# CC3000_WiFi_Breakout.net
KiCad netlist of a schematic drawn in EAGLE
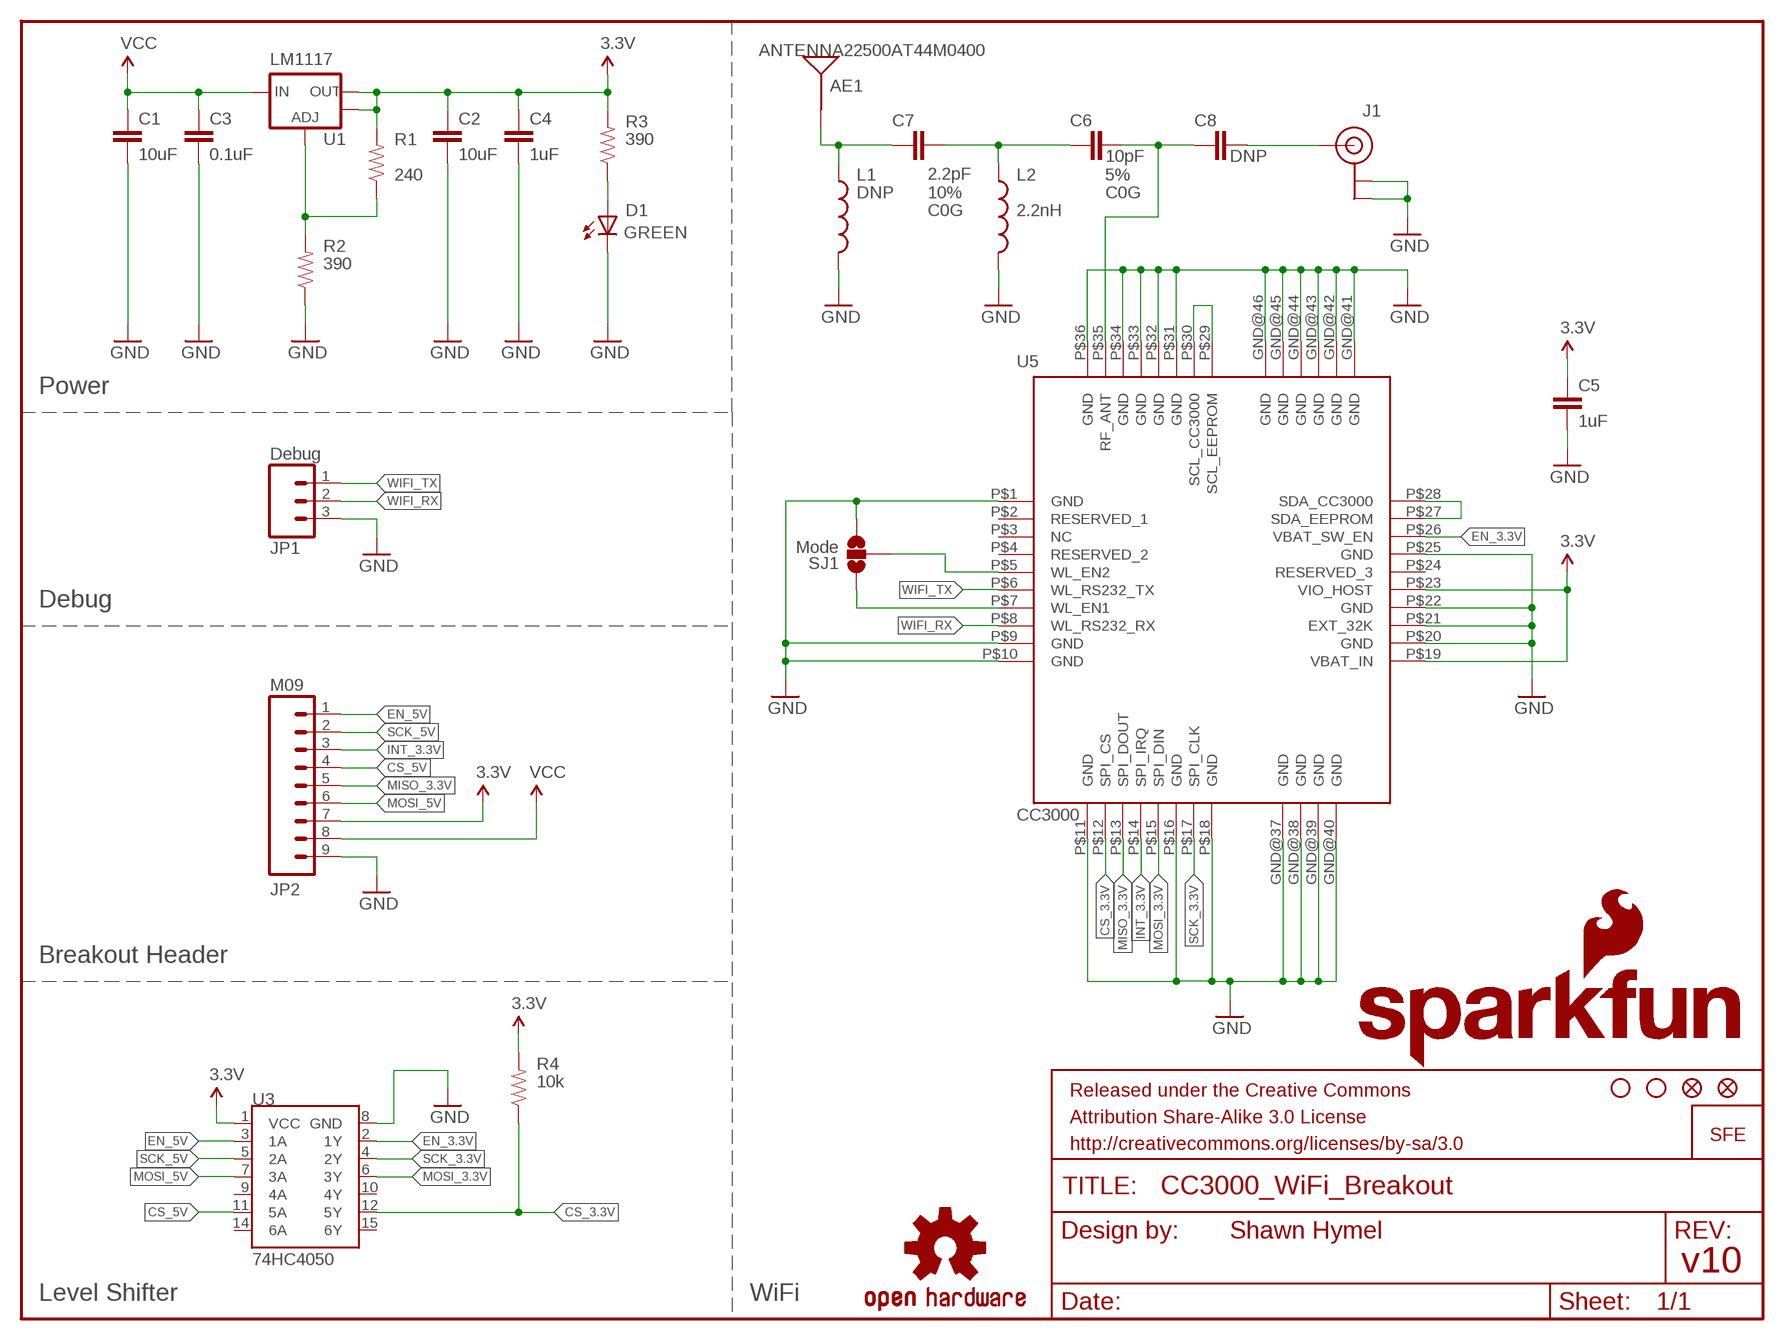
[diagram p0: schematic, sheet 1]

(export (version "E")
  (design (tool "Eeschema 10.0.6"))
  (components
    (comp (ref "AE1")
      (value "ANTENNA22500AT44M0400")
      (footprint "eagle-import:ANTENNA-CHIP_2500AT44M0400")
      (libsource (lib "eagle-import") (part "ANTENNA22500AT44M0400"))
    )
    (comp (ref "C1")
      (value "10uF")
      (footprint "eagle-import:0805")
      (libsource (lib "eagle-import") (part "CAP0805"))
    )
    (comp (ref "C2")
      (value "10uF")
      (footprint "eagle-import:0805")
      (libsource (lib "eagle-import") (part "CAP0805"))
    )
    (comp (ref "C3")
      (value "0.1uF")
      (footprint "eagle-import:0603-CAP")
      (libsource (lib "eagle-import") (part "CAP0603-CAP"))
    )
    (comp (ref "C4")
      (value "1uF")
      (footprint "eagle-import:0805")
      (libsource (lib "eagle-import") (part "CAP0805"))
    )
    (comp (ref "C5")
      (value "1uF")
      (footprint "eagle-import:0805")
      (libsource (lib "eagle-import") (part "CAP0805"))
    )
    (comp (ref "C6")
      (value "10pF")
      (footprint "eagle-import:0603-CAP")
      (fields (field (name "COEFF") "C0G") (field (name "TOL") "5%"))
      (libsource (lib "eagle-import") (part "CAP0603-CAP"))
    )
    (comp (ref "C7")
      (value "2.2pF")
      (footprint "eagle-import:0603-CAP")
      (fields (field (name "COEFF") "C0G") (field (name "TOL") "10%"))
      (libsource (lib "eagle-import") (part "CAP0603-CAP"))
    )
    (comp (ref "C8")
      (value "DNP")
      (footprint "eagle-import:0603-CAP")
      (libsource (lib "eagle-import") (part "CAP0603-CAP"))
    )
    (comp (ref "D1")
      (value "GREEN")
      (footprint "eagle-import:LED-0603")
      (libsource (lib "eagle-import") (part "LED-GREEN0603"))
    )
    (comp (ref "FID1")
      (value "FIDUCIAL1X2")
      (footprint "eagle-import:FIDUCIAL-1X2")
      (libsource (lib "eagle-import") (part "FIDUCIAL1X2"))
    )
    (comp (ref "FID2")
      (value "FIDUCIAL1X2")
      (footprint "eagle-import:FIDUCIAL-1X2")
      (libsource (lib "eagle-import") (part "FIDUCIAL1X2"))
    )
    (comp (ref "FRAME1")
      (value "FRAME-LETTER")
      (footprint "eagle-import:CREATIVE_COMMONS")
      (libsource (lib "eagle-import") (part "FRAME-LETTER"))
    )
    (comp (ref "J1")
      (value "U.FL")
      (footprint "eagle-import:U.FL")
      (libsource (lib "eagle-import") (part "U.FL"))
    )
    (comp (ref "JP1")
      (value "Debug")
      (footprint "eagle-import:1X03")
      (libsource (lib "eagle-import") (part "M03PTH"))
    )
    (comp (ref "JP2")
      (value "M09")
      (footprint "eagle-import:1X09")
      (libsource (lib "eagle-import") (part "M09"))
    )
    (comp (ref "L1")
      (value "DNP")
      (footprint "eagle-import:0603")
      (libsource (lib "eagle-import") (part "INDUCTOR0603"))
    )
    (comp (ref "L2")
      (value "2.2nH")
      (footprint "eagle-import:0603")
      (libsource (lib "eagle-import") (part "INDUCTOR0603"))
    )
    (comp (ref "LOGO1")
      (value "OSHW-LOGOS")
      (footprint "eagle-import:OSHW-LOGO-S")
      (libsource (lib "eagle-import") (part "OSHW-LOGOS"))
    )
    (comp (ref "LOGO3")
      (value "LOGO-SFESK")
      (footprint "eagle-import:SFE-LOGO-FLAME")
      (libsource (lib "eagle-import") (part "LOGO-SFESK"))
    )
    (comp (ref "LOGO4")
      (value "SFE_LOGO_NAME_FLAME.1_INCH")
      (footprint "eagle-import:SFE_LOGO_NAME_FLAME_.1")
      (libsource (lib "eagle-import") (part "SFE_LOGO_NAME_FLAME.1_INCH"))
    )
    (comp (ref "R1")
      (value "240")
      (footprint "eagle-import:0603-RES")
      (libsource (lib "eagle-import") (part "RESISTOR0603"))
    )
    (comp (ref "R2")
      (value "390")
      (footprint "eagle-import:0603-RES")
      (libsource (lib "eagle-import") (part "RESISTOR0603"))
    )
    (comp (ref "R3")
      (value "390")
      (footprint "eagle-import:0603-RES")
      (libsource (lib "eagle-import") (part "RESISTOR0603-RES"))
    )
    (comp (ref "R4")
      (value "10k")
      (footprint "eagle-import:0603-RES")
      (libsource (lib "eagle-import") (part "RESISTOR0603-RES"))
    )
    (comp (ref "SJ1")
      (value "Mode")
      (footprint "eagle-import:SJ_3_PASTE1&2")
      (libsource (lib "eagle-import") (part "SOLDERJUMPER_2WAYPASTE1&2"))
    )
    (comp (ref "STANDOFF1")
      (value "STAND-OFF")
      (footprint "eagle-import:STAND-OFF")
      (libsource (lib "eagle-import") (part "STAND-OFF"))
    )
    (comp (ref "STANDOFF2")
      (value "STAND-OFF")
      (footprint "eagle-import:STAND-OFF")
      (libsource (lib "eagle-import") (part "STAND-OFF"))
    )
    (comp (ref "U1")
      (value "LM1117")
      (footprint "eagle-import:SOT223")
      (libsource (lib "eagle-import") (part "V_REG_LM1117SOT223"))
    )
    (comp (ref "U3")
      (value "74HC4050")
      (footprint "eagle-import:SO016")
      (libsource (lib "eagle-import") (part "HEX_CONVERTER"))
    )
    (comp (ref "U5")
      (value "CC3000")
      (footprint "eagle-import:QFN-46_CC3000")
      (libsource (lib "eagle-import") (part "CC3000"))
    )
  )
  (nets
    (net (code "1") (name "3.3V") (class "Default")
      (node (ref "C2") (pin "1") (pinfunction "1_1") (pintype "passive"))
      (node (ref "C4") (pin "1") (pinfunction "1_1") (pintype "passive"))
      (node (ref "C5") (pin "1") (pinfunction "1_1") (pintype "passive"))
      (node (ref "JP2") (pin "7") (pinfunction "7_7") (pintype "passive"))
      (node (ref "R1") (pin "2") (pinfunction "2_2") (pintype "passive"))
      (node (ref "R3") (pin "2") (pinfunction "2_2") (pintype "passive"))
      (node (ref "R4") (pin "2") (pinfunction "2_2") (pintype "passive"))
      (node (ref "U1") (pin "2") (pinfunction "OUT_2") (pintype "output"))
      (node (ref "U1") (pin "4") (pinfunction "OUT_4") (pintype "output"))
      (node (ref "U3") (pin "1") (pinfunction "VCC_1") (pintype "bidirectional"))
      (node (ref "U5") (pin "P$19") (pinfunction "VBAT_IN_P$19") (pintype "bidirectional"))
      (node (ref "U5") (pin "P$23") (pinfunction "VIO_HOST_P$23") (pintype "bidirectional"))
    )
    (net (code "2") (name "CS_3.3V") (class "Default")
      (node (ref "R4") (pin "1") (pinfunction "1_1") (pintype "passive"))
      (node (ref "U3") (pin "12") (pinfunction "5Y_12") (pintype "bidirectional"))
      (node (ref "U5") (pin "P$12") (pinfunction "SPI_CS_P$12") (pintype "bidirectional"))
    )
    (net (code "3") (name "CS_5V") (class "Default")
      (node (ref "JP2") (pin "4") (pinfunction "4_4") (pintype "passive"))
      (node (ref "U3") (pin "11") (pinfunction "5A_11") (pintype "bidirectional"))
    )
    (net (code "4") (name "EN_3.3V") (class "Default")
      (node (ref "U3") (pin "2") (pinfunction "1Y_2") (pintype "bidirectional"))
      (node (ref "U5") (pin "P$26") (pinfunction "VBAT_SW_EN_P$26") (pintype "bidirectional"))
    )
    (net (code "5") (name "EN_5V") (class "Default")
      (node (ref "JP2") (pin "1") (pinfunction "1_1") (pintype "passive"))
      (node (ref "U3") (pin "3") (pinfunction "1A_3") (pintype "bidirectional"))
    )
    (net (code "6") (name "GND") (class "Default")
      (node (ref "C1") (pin "2") (pinfunction "2_2") (pintype "passive"))
      (node (ref "C2") (pin "2") (pinfunction "2_2") (pintype "passive"))
      (node (ref "C3") (pin "2") (pinfunction "2_2") (pintype "passive"))
      (node (ref "C4") (pin "2") (pinfunction "2_2") (pintype "passive"))
      (node (ref "C5") (pin "2") (pinfunction "2_2") (pintype "passive"))
      (node (ref "D1") (pin "C") (pinfunction "C_C") (pintype "passive"))
      (node (ref "J1") (pin "P$1") (pinfunction "GND_P$1") (pintype "bidirectional"))
      (node (ref "J1") (pin "P$2") (pinfunction "GND_P$2") (pintype "bidirectional"))
      (node (ref "JP1") (pin "3") (pinfunction "3_3") (pintype "passive"))
      (node (ref "JP2") (pin "9") (pinfunction "9_9") (pintype "passive"))
      (node (ref "L1") (pin "2") (pinfunction "2_2") (pintype "passive"))
      (node (ref "L2") (pin "2") (pinfunction "2_2") (pintype "passive"))
      (node (ref "R2") (pin "1") (pinfunction "1_1") (pintype "passive"))
      (node (ref "SJ1") (pin "3") (pinfunction "3_3") (pintype "passive"))
      (node (ref "U3") (pin "8") (pinfunction "GND_8") (pintype "bidirectional"))
      (node (ref "U5") (pin "GND@37") (pinfunction "GND_GND@37") (pintype "bidirectional"))
      (node (ref "U5") (pin "GND@38") (pinfunction "GND_GND@38") (pintype "bidirectional"))
      (node (ref "U5") (pin "GND@39") (pinfunction "GND_GND@39") (pintype "bidirectional"))
      (node (ref "U5") (pin "GND@40") (pinfunction "GND_GND@40") (pintype "bidirectional"))
      (node (ref "U5") (pin "GND@41") (pinfunction "GND_GND@41") (pintype "bidirectional"))
      (node (ref "U5") (pin "GND@42") (pinfunction "GND_GND@42") (pintype "bidirectional"))
      (node (ref "U5") (pin "GND@43") (pinfunction "GND_GND@43") (pintype "bidirectional"))
      (node (ref "U5") (pin "GND@44") (pinfunction "GND_GND@44") (pintype "bidirectional"))
      (node (ref "U5") (pin "GND@45") (pinfunction "GND_GND@45") (pintype "bidirectional"))
      (node (ref "U5") (pin "GND@46") (pinfunction "GND_GND@46") (pintype "bidirectional"))
      (node (ref "U5") (pin "P$1") (pinfunction "GND_P$1") (pintype "bidirectional"))
      (node (ref "U5") (pin "P$10") (pinfunction "GND_P$10") (pintype "bidirectional"))
      (node (ref "U5") (pin "P$11") (pinfunction "GND_P$11") (pintype "bidirectional"))
      (node (ref "U5") (pin "P$16") (pinfunction "GND_P$16") (pintype "bidirectional"))
      (node (ref "U5") (pin "P$18") (pinfunction "GND_P$18") (pintype "bidirectional"))
      (node (ref "U5") (pin "P$20") (pinfunction "GND_P$20") (pintype "bidirectional"))
      (node (ref "U5") (pin "P$21") (pinfunction "EXT_32K_P$21") (pintype "bidirectional"))
      (node (ref "U5") (pin "P$22") (pinfunction "GND_P$22") (pintype "bidirectional"))
      (node (ref "U5") (pin "P$25") (pinfunction "GND_P$25") (pintype "bidirectional"))
      (node (ref "U5") (pin "P$31") (pinfunction "GND_P$31") (pintype "bidirectional"))
      (node (ref "U5") (pin "P$32") (pinfunction "GND_P$32") (pintype "bidirectional"))
      (node (ref "U5") (pin "P$33") (pinfunction "GND_P$33") (pintype "bidirectional"))
      (node (ref "U5") (pin "P$34") (pinfunction "GND_P$34") (pintype "bidirectional"))
      (node (ref "U5") (pin "P$36") (pinfunction "GND_P$36") (pintype "bidirectional"))
      (node (ref "U5") (pin "P$9") (pinfunction "GND_P$9") (pintype "bidirectional"))
    )
    (net (code "7") (name "INT_3.3V") (class "Default")
      (node (ref "JP2") (pin "3") (pinfunction "3_3") (pintype "passive"))
      (node (ref "U5") (pin "P$14") (pinfunction "SPI_IRQ_P$14") (pintype "bidirectional"))
    )
    (net (code "8") (name "MISO_3.3V") (class "Default")
      (node (ref "JP2") (pin "5") (pinfunction "5_5") (pintype "passive"))
      (node (ref "U5") (pin "P$13") (pinfunction "SPI_DOUT_P$13") (pintype "bidirectional"))
    )
    (net (code "9") (name "MOSI_3.3V") (class "Default")
      (node (ref "U3") (pin "6") (pinfunction "3Y_6") (pintype "bidirectional"))
      (node (ref "U5") (pin "P$15") (pinfunction "SPI_DIN_P$15") (pintype "bidirectional"))
    )
    (net (code "10") (name "MOSI_5V") (class "Default")
      (node (ref "JP2") (pin "6") (pinfunction "6_6") (pintype "passive"))
      (node (ref "U3") (pin "7") (pinfunction "3A_7") (pintype "bidirectional"))
    )
    (net (code "11") (name "Net-(AE1-SIGNAL)") (class "Default")
      (node (ref "AE1") (pin "FEED") (pinfunction "SIGNAL_FEED") (pintype "bidirectional"))
      (node (ref "C7") (pin "1") (pinfunction "1_1") (pintype "passive"))
      (node (ref "L1") (pin "1") (pinfunction "1_1") (pintype "passive"))
    )
    (net (code "12") (name "Net-(C6-Pad1)") (class "Default")
      (node (ref "C6") (pin "1") (pinfunction "1_1") (pintype "passive"))
      (node (ref "C7") (pin "2") (pinfunction "2_2") (pintype "passive"))
      (node (ref "L2") (pin "1") (pinfunction "1_1") (pintype "passive"))
    )
    (net (code "13") (name "Net-(D1-PadA)") (class "Default")
      (node (ref "D1") (pin "A") (pinfunction "A_A") (pintype "passive"))
      (node (ref "R3") (pin "1") (pinfunction "1_1") (pintype "passive"))
    )
    (net (code "14") (name "Net-(J1-SIGNAL)") (class "Default")
      (node (ref "C8") (pin "2") (pinfunction "2_2") (pintype "passive"))
      (node (ref "J1") (pin "P$3") (pinfunction "SIGNAL_P$3") (pintype "bidirectional"))
    )
    (net (code "15") (name "Net-(U1-ADJ)") (class "Default")
      (node (ref "R1") (pin "1") (pinfunction "1_1") (pintype "passive"))
      (node (ref "R2") (pin "2") (pinfunction "2_2") (pintype "passive"))
      (node (ref "U1") (pin "1") (pinfunction "ADJ_1") (pintype "input"))
    )
    (net (code "16") (name "Net-(U5-RF_ANT)") (class "Default")
      (node (ref "C6") (pin "2") (pinfunction "2_2") (pintype "passive"))
      (node (ref "C8") (pin "1") (pinfunction "1_1") (pintype "passive"))
      (node (ref "U5") (pin "P$35") (pinfunction "RF_ANT_P$35") (pintype "bidirectional"))
    )
    (net (code "17") (name "Net-(U5-SCL_CC3000)") (class "Default")
      (node (ref "U5") (pin "P$29") (pinfunction "SCL_EEPROM_P$29") (pintype "bidirectional"))
      (node (ref "U5") (pin "P$30") (pinfunction "SCL_CC3000_P$30") (pintype "bidirectional"))
    )
    (net (code "18") (name "Net-(U5-SDA_CC3000)") (class "Default")
      (node (ref "U5") (pin "P$27") (pinfunction "SDA_EEPROM_P$27") (pintype "bidirectional"))
      (node (ref "U5") (pin "P$28") (pinfunction "SDA_CC3000_P$28") (pintype "bidirectional"))
    )
    (net (code "19") (name "Net-(U5-WL_EN1)") (class "Default")
      (node (ref "SJ1") (pin "1") (pinfunction "1_1") (pintype "passive"))
      (node (ref "U5") (pin "P$7") (pinfunction "WL_EN1_P$7") (pintype "bidirectional"))
    )
    (net (code "20") (name "Net-(U5-WL_EN2)") (class "Default")
      (node (ref "SJ1") (pin "2") (pinfunction "2_2") (pintype "passive"))
      (node (ref "U5") (pin "P$5") (pinfunction "WL_EN2_P$5") (pintype "bidirectional"))
    )
    (net (code "21") (name "SCK_3.3V") (class "Default")
      (node (ref "U3") (pin "4") (pinfunction "2Y_4") (pintype "bidirectional"))
      (node (ref "U5") (pin "P$17") (pinfunction "SPI_CLK_P$17") (pintype "bidirectional"))
    )
    (net (code "22") (name "SCK_5V") (class "Default")
      (node (ref "JP2") (pin "2") (pinfunction "2_2") (pintype "passive"))
      (node (ref "U3") (pin "5") (pinfunction "2A_5") (pintype "bidirectional"))
    )
    (net (code "23") (name "VCC") (class "Default")
      (node (ref "C1") (pin "1") (pinfunction "1_1") (pintype "passive"))
      (node (ref "C3") (pin "1") (pinfunction "1_1") (pintype "passive"))
      (node (ref "JP2") (pin "8") (pinfunction "8_8") (pintype "passive"))
      (node (ref "U1") (pin "3") (pinfunction "IN_3") (pintype "input"))
    )
    (net (code "24") (name "WIFI_RX") (class "Default")
      (node (ref "JP1") (pin "2") (pinfunction "2_2") (pintype "passive"))
      (node (ref "U5") (pin "P$8") (pinfunction "WL_RS232_RX_P$8") (pintype "bidirectional"))
    )
    (net (code "25") (name "WIFI_TX") (class "Default")
      (node (ref "JP1") (pin "1") (pinfunction "1_1") (pintype "passive"))
      (node (ref "U5") (pin "P$6") (pinfunction "WL_RS232_TX_P$6") (pintype "bidirectional"))
    )
    (net (code "26") (name "unconnected-(U3-4A-Pad9)") (class "Default")
      (node (ref "U3") (pin "9") (pinfunction "4A_9") (pintype "bidirectional"))
    )
    (net (code "27") (name "unconnected-(U3-4Y-Pad10)") (class "Default")
      (node (ref "U3") (pin "10") (pinfunction "4Y_10") (pintype "bidirectional"))
    )
    (net (code "28") (name "unconnected-(U3-6A-Pad14)") (class "Default")
      (node (ref "U3") (pin "14") (pinfunction "6A_14") (pintype "bidirectional"))
    )
    (net (code "29") (name "unconnected-(U3-6Y-Pad15)") (class "Default")
      (node (ref "U3") (pin "15") (pinfunction "6Y_15") (pintype "bidirectional"))
    )
    (net (code "30") (name "unconnected-(U5-NC-PadP$3)") (class "Default")
      (node (ref "U5") (pin "P$3") (pinfunction "NC_P$3") (pintype "bidirectional"))
    )
    (net (code "31") (name "unconnected-(U5-RESERVED_1-PadP$2)") (class "Default")
      (node (ref "U5") (pin "P$2") (pinfunction "RESERVED_1_P$2") (pintype "bidirectional"))
    )
    (net (code "32") (name "unconnected-(U5-RESERVED_2-PadP$4)") (class "Default")
      (node (ref "U5") (pin "P$4") (pinfunction "RESERVED_2_P$4") (pintype "bidirectional"))
    )
    (net (code "33") (name "unconnected-(U5-RESERVED_3-PadP$24)") (class "Default")
      (node (ref "U5") (pin "P$24") (pinfunction "RESERVED_3_P$24") (pintype "bidirectional"))
    )
  )
)
